# IR_Schreib_Lesekopf_TTL_Neu_V1.net
KiCad netlist of a schematic drawn in EAGLE
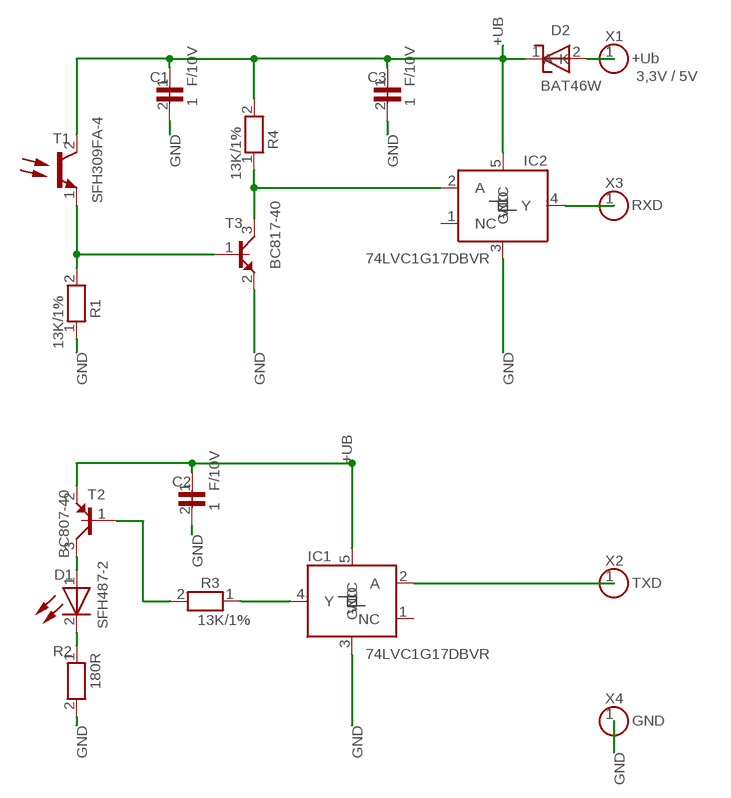
[diagram p0: schematic, sheet 1]

(export (version "E")
  (design (tool "Eeschema 10.0.6"))
  (components
    (comp (ref "C1")
      (value "1�F/10V")
      (footprint "eagle-import:0603")
      (libsource (lib "eagle-import") (part "1�F/10V"))
    )
    (comp (ref "C2")
      (value "1�F/10V")
      (footprint "eagle-import:0603")
      (libsource (lib "eagle-import") (part "1�F/10V"))
    )
    (comp (ref "C3")
      (value "1�F/10V")
      (footprint "eagle-import:0603")
      (libsource (lib "eagle-import") (part "1�F/10V"))
    )
    (comp (ref "D1")
      (value "SFH487-2")
      (footprint "eagle-import:LED_3MM")
      (libsource (lib "eagle-import") (part "SFH487-2"))
    )
    (comp (ref "D2")
      (value "BAT46W")
      (footprint "eagle-import:SOD123")
      (libsource (lib "eagle-import") (part "BAT46W"))
    )
    (comp (ref "IC1")
      (value "74LVC1G17DBVR")
      (footprint "eagle-import:SOT23_5")
      (libsource (lib "eagle-import") (part "74LVC1G17DBVR"))
    )
    (comp (ref "IC2")
      (value "74LVC1G17DBVR")
      (footprint "eagle-import:SOT23_5")
      (libsource (lib "eagle-import") (part "74LVC1G17DBVR"))
    )
    (comp (ref "R1")
      (value "13K/1%")
      (footprint "eagle-import:0603")
      (libsource (lib "eagle-import") (part "13K/1%"))
    )
    (comp (ref "R2")
      (value "180R")
      (footprint "eagle-import:0603")
      (libsource (lib "eagle-import") (part "180R"))
    )
    (comp (ref "R3")
      (value "13K/1%")
      (footprint "eagle-import:0603")
      (libsource (lib "eagle-import") (part "13K/1%"))
    )
    (comp (ref "R4")
      (value "13K/1%")
      (footprint "eagle-import:0603")
      (libsource (lib "eagle-import") (part "13K/1%"))
    )
    (comp (ref "T1")
      (value "SFH309FA-4")
      (footprint "eagle-import:LED_3MM")
      (libsource (lib "eagle-import") (part "SFH309FA-4"))
    )
    (comp (ref "T2")
      (value "BC807-40")
      (footprint "eagle-import:SOT23_3")
      (libsource (lib "eagle-import") (part "BC807-40"))
    )
    (comp (ref "T3")
      (value "BC817-40")
      (footprint "eagle-import:SOT23_3")
      (libsource (lib "eagle-import") (part "BC817-40"))
    )
    (comp (ref "X1")
      (value "+Ub")
      (footprint "eagle-import:LOETPUNKT")
      (libsource (lib "eagle-import") (part "+UB"))
    )
    (comp (ref "X2")
      (value "TXD")
      (footprint "eagle-import:LOETPUNKT")
      (libsource (lib "eagle-import") (part "TXD"))
    )
    (comp (ref "X3")
      (value "RXD")
      (footprint "eagle-import:LOETPUNKT")
      (libsource (lib "eagle-import") (part "RXD"))
    )
    (comp (ref "X4")
      (value "GND")
      (footprint "eagle-import:LOETPUNKT")
      (libsource (lib "eagle-import") (part "GND"))
    )
  )
  (nets
    (net (code "1") (name "/+UB") (class "Default")
      (node (ref "C1") (pin "1") (pinfunction "1_1") (pintype "passive"))
      (node (ref "C2") (pin "1") (pinfunction "1_1") (pintype "passive"))
      (node (ref "C3") (pin "1") (pinfunction "1_1") (pintype "passive"))
      (node (ref "D2") (pin "1") (pinfunction "K_1") (pintype "passive"))
      (node (ref "IC1") (pin "5") (pinfunction "VCC_5") (pintype "passive"))
      (node (ref "IC2") (pin "5") (pinfunction "VCC_5") (pintype "passive"))
      (node (ref "R4") (pin "2") (pinfunction "2_2") (pintype "passive"))
      (node (ref "T1") (pin "2") (pinfunction "2_2") (pintype "passive"))
      (node (ref "T2") (pin "2") (pinfunction "2_2") (pintype "passive"))
    )
    (net (code "2") (name "/GND") (class "Default")
      (node (ref "C1") (pin "2") (pinfunction "2_2") (pintype "passive"))
      (node (ref "C2") (pin "2") (pinfunction "2_2") (pintype "passive"))
      (node (ref "C3") (pin "2") (pinfunction "2_2") (pintype "passive"))
      (node (ref "IC1") (pin "3") (pinfunction "GND_3") (pintype "passive"))
      (node (ref "IC2") (pin "3") (pinfunction "GND_3") (pintype "passive"))
      (node (ref "R1") (pin "1") (pinfunction "1_1") (pintype "passive"))
      (node (ref "R2") (pin "2") (pinfunction "2_2") (pintype "passive"))
      (node (ref "T3") (pin "2") (pinfunction "2_2") (pintype "passive"))
      (node (ref "X4") (pin "1") (pinfunction "1_1") (pintype "passive"))
    )
    (net (code "3") (name "Net-(D1-Pad1)") (class "Default")
      (node (ref "D1") (pin "1") (pinfunction "1_1") (pintype "passive"))
      (node (ref "T2") (pin "3") (pinfunction "3_3") (pintype "passive"))
    )
    (net (code "4") (name "Net-(D1-Pad2)") (class "Default")
      (node (ref "D1") (pin "2") (pinfunction "2_2") (pintype "passive"))
      (node (ref "R2") (pin "1") (pinfunction "1_1") (pintype "passive"))
    )
    (net (code "5") (name "Net-(D2-A)") (class "Default")
      (node (ref "D2") (pin "2") (pinfunction "A_2") (pintype "passive"))
      (node (ref "X1") (pin "1") (pinfunction "1_1") (pintype "passive"))
    )
    (net (code "6") (name "Net-(IC1-A)") (class "Default")
      (node (ref "IC1") (pin "2") (pinfunction "A_2") (pintype "passive"))
      (node (ref "X2") (pin "1") (pinfunction "1_1") (pintype "passive"))
    )
    (net (code "7") (name "Net-(IC1-Y)") (class "Default")
      (node (ref "IC1") (pin "4") (pinfunction "Y_4") (pintype "passive"))
      (node (ref "R3") (pin "1") (pinfunction "1_1") (pintype "passive"))
    )
    (net (code "8") (name "Net-(IC2-A)") (class "Default")
      (node (ref "IC2") (pin "2") (pinfunction "A_2") (pintype "passive"))
      (node (ref "R4") (pin "1") (pinfunction "1_1") (pintype "passive"))
      (node (ref "T3") (pin "3") (pinfunction "3_3") (pintype "passive"))
    )
    (net (code "9") (name "Net-(IC2-Y)") (class "Default")
      (node (ref "IC2") (pin "4") (pinfunction "Y_4") (pintype "passive"))
      (node (ref "X3") (pin "1") (pinfunction "1_1") (pintype "passive"))
    )
    (net (code "10") (name "Net-(R1-Pad2)") (class "Default")
      (node (ref "R1") (pin "2") (pinfunction "2_2") (pintype "passive"))
      (node (ref "T1") (pin "1") (pinfunction "1_1") (pintype "passive"))
      (node (ref "T3") (pin "1") (pinfunction "1_1") (pintype "passive"))
    )
    (net (code "11") (name "Net-(R3-Pad2)") (class "Default")
      (node (ref "R3") (pin "2") (pinfunction "2_2") (pintype "passive"))
      (node (ref "T2") (pin "1") (pinfunction "1_1") (pintype "passive"))
    )
    (net (code "12") (name "unconnected-(IC1-NC-Pad1)") (class "Default")
      (node (ref "IC1") (pin "1") (pinfunction "NC_1") (pintype "passive"))
    )
    (net (code "13") (name "unconnected-(IC2-NC-Pad1)") (class "Default")
      (node (ref "IC2") (pin "1") (pinfunction "NC_1") (pintype "passive"))
    )
  )
)
